# E_ink_stuff.net
KiCad netlist of a schematic drawn in Altium Designer
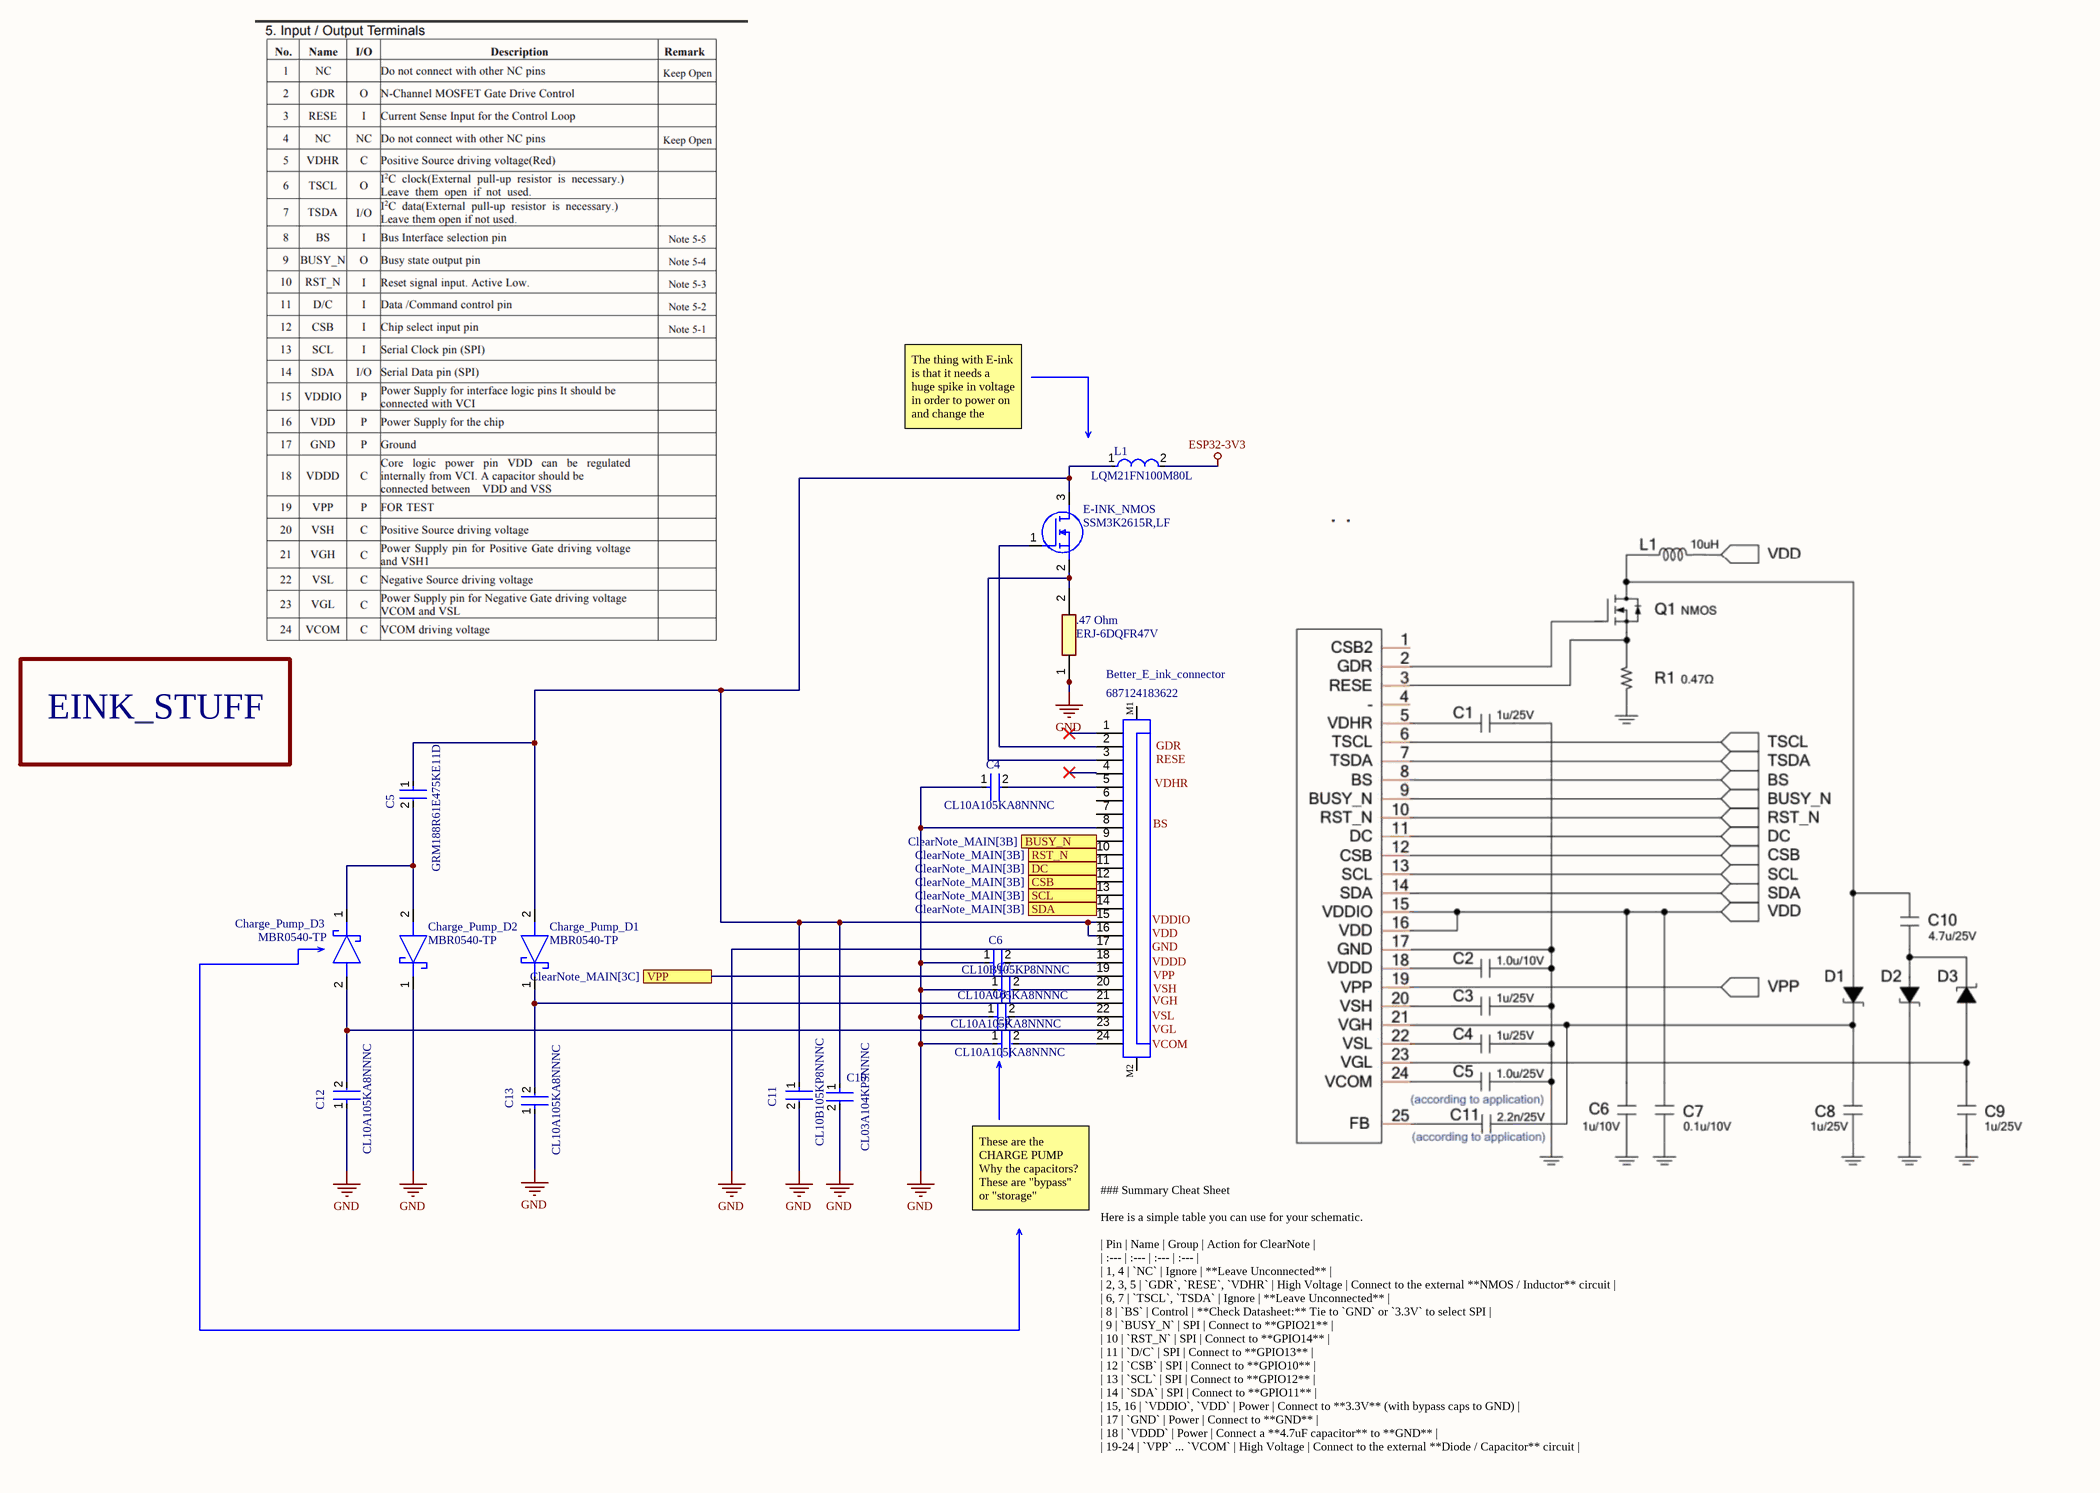
[diagram p0: E_ink_stuff.SchDoc]

(export (version "E")
  (design (tool "Eeschema 10.0.6"))
  (components
    (comp (ref ".47 Ohm")
      (value "ERJ-6DQFR47V")
      (footprint "SamacSys:ERJ6_B_BW_R_LW_CW_D")
      (description "Resistor")
      (fields (field (name "MOUSER PART NUMBER") "667-ERJ-6DQFR47V"))
      (libsource (lib "*") (part "ERJ-6DQFR47V"))
    )
    (comp (ref "Better_E_ink_connector")
      (value "687124183622")
      (footprint "687124183622")
      (libsource (lib "Altium Content Vault") (part "FPC - 24P - 2MP"))
    )
    (comp (ref "C4")
      (value "CL10A105KA8NNNC")
      (footprint "FP-CL10-IPC_C")
      (description "Cap Ceramic 1uF 25V X5R ±10% Pad SMD 0603 +85°C T/R")
      (fields (field (name "VOLTAGE") "25V") (field (name "TOLERANCE") "10%"))
      (libsource (lib "Altium Content Vault") (part "b4654b650e69147ec39a6b967a45e02"))
    )
    (comp (ref "C5")
      (value "GRM188R61E475KE11D")
      (footprint "FP-GRM188-0_15-IPC_C")
      (description "Chip Multilayer Ceramic Capacitors for General Purpose, 0603, 4.7uF, X5R, 15%, 10%, 25V")
      (fields (field (name "VOLTAGE") "25V") (field (name "TOLERANCE") "10%"))
      (libsource (lib "Altium Content Vault") (part "02cd4be3c70576c341d710602a673aa"))
    )
    (comp (ref "C6")
      (value "CL10B105KP8NNNC")
      (footprint "FP-CL10-IPC_C")
      (description "Cap Ceramic 1uF 10V X7R ±10% Pad SMD 0603 +125°C T/R")
      (fields (field (name "TOLERANCE") "10%"))
      (libsource (lib "Altium Content Vault") (part "b4654b650e69147ec39a6b967a45e02"))
    )
    (comp (ref "C7")
      (value "CL10A105KA8NNNC")
      (footprint "FP-CL10-IPC_C")
      (description "Cap Ceramic 1uF 25V X5R ±10% Pad SMD 0603 +85°C T/R")
      (fields (field (name "VOLTAGE") "25V") (field (name "TOLERANCE") "10%"))
      (libsource (lib "Altium Content Vault") (part "b4654b650e69147ec39a6b967a45e02"))
    )
    (comp (ref "C8")
      (value "CL10A105KA8NNNC")
      (footprint "FP-CL10-IPC_C")
      (description "Cap Ceramic 1uF 25V X5R ±10% Pad SMD 0603 +85°C T/R")
      (fields (field (name "VOLTAGE") "25V") (field (name "TOLERANCE") "10%"))
      (libsource (lib "Altium Content Vault") (part "b4654b650e69147ec39a6b967a45e02"))
    )
    (comp (ref "C9")
      (value "CL10A105KA8NNNC")
      (footprint "FP-CL10-IPC_C")
      (description "Cap Ceramic 1uF 25V X5R ±10% Pad SMD 0603 +85°C T/R")
      (fields (field (name "VOLTAGE") "25V") (field (name "TOLERANCE") "10%"))
      (libsource (lib "Altium Content Vault") (part "b4654b650e69147ec39a6b967a45e02"))
    )
    (comp (ref "C10")
      (value "CL03A104KP3NNNC")
      (footprint "FP-CL03-IPC_C")
      (description "Cap Ceramic 100nF 10V X5R ±10% Pad SMD 0201 +85°C T/R")
      (fields (field (name "TOLERANCE") "10%"))
      (libsource (lib "Altium Content Vault") (part "b4654b650e69147ec39a6b967a45e02"))
    )
    (comp (ref "C11")
      (value "CL10B105KP8NNNC")
      (footprint "FP-CL10-IPC_C")
      (description "Cap Ceramic 1uF 10V X7R ±10% Pad SMD 0603 +125°C T/R")
      (fields (field (name "TOLERANCE") "10%"))
      (libsource (lib "Altium Content Vault") (part "b4654b650e69147ec39a6b967a45e02"))
    )
    (comp (ref "C12")
      (value "CL10A105KA8NNNC")
      (footprint "FP-CL10-IPC_C")
      (description "Cap Ceramic 1uF 25V X5R ±10% Pad SMD 0603 +85°C T/R")
      (fields (field (name "VOLTAGE") "25V") (field (name "TOLERANCE") "10%"))
      (libsource (lib "Altium Content Vault") (part "b4654b650e69147ec39a6b967a45e02"))
    )
    (comp (ref "C13")
      (value "CL10A105KA8NNNC")
      (footprint "FP-CL10-IPC_C")
      (description "Cap Ceramic 1uF 25V X5R ±10% Pad SMD 0603 +85°C T/R")
      (fields (field (name "VOLTAGE") "25V") (field (name "TOLERANCE") "10%"))
      (libsource (lib "Altium Content Vault") (part "b4654b650e69147ec39a6b967a45e02"))
    )
    (comp (ref "Charge_Pump_D1")
      (value "MBR0540-TP")
      (footprint "SamacSys:SOD3716X135N")
      (description "Schottky Diode")
      (fields (field (name "MOUSER PART NUMBER") "833-MBR0540-TP"))
      (libsource (lib "*") (part "MBR0540-TP"))
    )
    (comp (ref "Charge_Pump_D2")
      (value "MBR0540-TP")
      (footprint "SamacSys:SOD3716X135N")
      (description "Schottky Diode")
      (fields (field (name "MOUSER PART NUMBER") "833-MBR0540-TP"))
      (libsource (lib "*") (part "MBR0540-TP"))
    )
    (comp (ref "Charge_Pump_D3")
      (value "MBR0540-TP")
      (footprint "SamacSys:SOD3716X135N")
      (description "Schottky Diode")
      (fields (field (name "MOUSER PART NUMBER") "833-MBR0540-TP"))
      (libsource (lib "*") (part "MBR0540-TP"))
    )
    (comp (ref "E-INK_NMOS")
      (value "SSM3K2615R,LF")
      (footprint "SamacSys:SOTFL95P240X88-3N")
      (description "MOSFET (N-Channel)")
      (fields (field (name "MOUSER PART NUMBER") "757-SSM3K2615RLF"))
      (libsource (lib "*") (part "SSM3K2615R,LF"))
    )
    (comp (ref "L1")
      (value "LQM21FN100M80L")
      (footprint "FP-LQM21DH_70-IPC_C")
      (description "Multilayer Type Inductor for Power Lines, 0805 (2012), 10μH, 20%, 0.39Ω, 100mA")
      (fields (field (name "TOLERANCE") "20%"))
      (libsource (lib "Altium Content Vault") (part "725321dda6339637d4d059423bc1c3c"))
    )
  )
  (nets
    (net (code "1") (name "/BUSY_N") (class "Default")
      (node (ref "Better_E_ink_connector") (pin "9") (pinfunction "9_9") (pintype "passive"))
    )
    (net (code "2") (name "/CSB") (class "Default")
      (node (ref "Better_E_ink_connector") (pin "12") (pinfunction "12_12") (pintype "passive"))
    )
    (net (code "3") (name "/DC") (class "Default")
      (node (ref "Better_E_ink_connector") (pin "11") (pinfunction "11_11") (pintype "passive"))
    )
    (net (code "4") (name "/RST_N") (class "Default")
      (node (ref "Better_E_ink_connector") (pin "10") (pinfunction "10_10") (pintype "passive"))
    )
    (net (code "5") (name "/SCL") (class "Default")
      (node (ref "Better_E_ink_connector") (pin "13") (pinfunction "13_13") (pintype "passive"))
    )
    (net (code "6") (name "/SDA") (class "Default")
      (node (ref "Better_E_ink_connector") (pin "14") (pinfunction "14_14") (pintype "passive"))
    )
    (net (code "7") (name "/VPP") (class "Default")
      (node (ref "Better_E_ink_connector") (pin "19") (pinfunction "19_19") (pintype "passive"))
    )
    (net (code "8") (name "ESP32-3V3") (class "Default")
      (node (ref "L1") (pin "2") (pinfunction "2_2") (pintype "passive"))
    )
    (net (code "9") (name "GND") (class "Default")
      (node (ref ".47 Ohm") (pin "1") (pinfunction "1_1") (pintype "passive"))
      (node (ref "Better_E_ink_connector") (pin "17") (pinfunction "17_17") (pintype "passive"))
      (node (ref "Better_E_ink_connector") (pin "8") (pinfunction "8_8") (pintype "passive"))
      (node (ref "C10") (pin "2") (pinfunction "2_2") (pintype "passive"))
      (node (ref "C11") (pin "2") (pinfunction "2_2") (pintype "passive"))
      (node (ref "C12") (pin "1") (pinfunction "1_1") (pintype "passive"))
      (node (ref "C13") (pin "1") (pinfunction "1_1") (pintype "passive"))
      (node (ref "C4") (pin "1") (pinfunction "1_1") (pintype "passive"))
      (node (ref "C6") (pin "1") (pinfunction "1_1") (pintype "passive"))
      (node (ref "C7") (pin "1") (pinfunction "1_1") (pintype "passive"))
      (node (ref "C8") (pin "1") (pinfunction "1_1") (pintype "passive"))
      (node (ref "C9") (pin "1") (pinfunction "1_1") (pintype "passive"))
      (node (ref "Charge_Pump_D2") (pin "1") (pinfunction "K_1") (pintype "passive"))
    )
    (net (code "10") (name "Net-(Better_E_ink_connector-Pad5)") (class "Default")
      (node (ref "Better_E_ink_connector") (pin "5") (pinfunction "5_5") (pintype "passive"))
      (node (ref "C4") (pin "2") (pinfunction "2_2") (pintype "passive"))
    )
    (net (code "11") (name "Net-(Better_E_ink_connector-Pad18)") (class "Default")
      (node (ref "Better_E_ink_connector") (pin "18") (pinfunction "18_18") (pintype "passive"))
      (node (ref "C6") (pin "2") (pinfunction "2_2") (pintype "passive"))
    )
    (net (code "12") (name "Net-(Better_E_ink_connector-Pad20)") (class "Default")
      (node (ref "Better_E_ink_connector") (pin "20") (pinfunction "20_20") (pintype "passive"))
      (node (ref "C7") (pin "2") (pinfunction "2_2") (pintype "passive"))
    )
    (net (code "13") (name "Net-(Better_E_ink_connector-Pad22)") (class "Default")
      (node (ref "Better_E_ink_connector") (pin "22") (pinfunction "22_22") (pintype "passive"))
      (node (ref "C8") (pin "2") (pinfunction "2_2") (pintype "passive"))
    )
    (net (code "14") (name "Net-(Better_E_ink_connector-Pad24)") (class "Default")
      (node (ref "Better_E_ink_connector") (pin "24") (pinfunction "24_24") (pintype "passive"))
      (node (ref "C9") (pin "2") (pinfunction "2_2") (pintype "passive"))
    )
    (net (code "15") (name "Net-(Charge_Pump_D1-A)") (class "Default")
      (node (ref "Better_E_ink_connector") (pin "15") (pinfunction "15_15") (pintype "passive"))
      (node (ref "Better_E_ink_connector") (pin "16") (pinfunction "16_16") (pintype "passive"))
      (node (ref "C10") (pin "1") (pinfunction "1_1") (pintype "passive"))
      (node (ref "C11") (pin "1") (pinfunction "1_1") (pintype "passive"))
      (node (ref "C5") (pin "1") (pinfunction "1_1") (pintype "passive"))
      (node (ref "Charge_Pump_D1") (pin "2") (pinfunction "A_2") (pintype "passive"))
      (node (ref "E-INK_NMOS") (pin "3") (pinfunction "D_3") (pintype "passive"))
      (node (ref "L1") (pin "1") (pinfunction "1_1") (pintype "passive"))
    )
    (net (code "16") (name "Net-(Charge_Pump_D1-K)") (class "Default")
      (node (ref "Better_E_ink_connector") (pin "21") (pinfunction "21_21") (pintype "passive"))
      (node (ref "C13") (pin "2") (pinfunction "2_2") (pintype "passive"))
      (node (ref "Charge_Pump_D1") (pin "1") (pinfunction "K_1") (pintype "passive"))
    )
    (net (code "17") (name "Net-(Charge_Pump_D2-A)") (class "Default")
      (node (ref "C5") (pin "2") (pinfunction "2_2") (pintype "passive"))
      (node (ref "Charge_Pump_D2") (pin "2") (pinfunction "A_2") (pintype "passive"))
      (node (ref "Charge_Pump_D3") (pin "1") (pinfunction "K_1") (pintype "passive"))
    )
    (net (code "18") (name "Net-(Charge_Pump_D3-A)") (class "Default")
      (node (ref "Better_E_ink_connector") (pin "23") (pinfunction "23_23") (pintype "passive"))
      (node (ref "C12") (pin "2") (pinfunction "2_2") (pintype "passive"))
      (node (ref "Charge_Pump_D3") (pin "2") (pinfunction "A_2") (pintype "passive"))
    )
    (net (code "19") (name "Net-(E-INK_NMOS-G)") (class "Default")
      (node (ref "Better_E_ink_connector") (pin "2") (pinfunction "2_2") (pintype "passive"))
      (node (ref "E-INK_NMOS") (pin "1") (pinfunction "G_1") (pintype "passive"))
    )
    (net (code "20") (name "Net-(E-INK_NMOS-S)") (class "Default")
      (node (ref ".47 Ohm") (pin "2") (pinfunction "2_2") (pintype "passive"))
      (node (ref "Better_E_ink_connector") (pin "3") (pinfunction "3_3") (pintype "passive"))
      (node (ref "E-INK_NMOS") (pin "2") (pinfunction "S_2") (pintype "passive"))
    )
    (net (code "21") (name "unconnected-(Better_E_ink_connector-Pad1)") (class "Default")
      (node (ref "Better_E_ink_connector") (pin "1") (pinfunction "1_1") (pintype "passive+no_connect"))
    )
    (net (code "22") (name "unconnected-(Better_E_ink_connector-Pad4)") (class "Default")
      (node (ref "Better_E_ink_connector") (pin "4") (pinfunction "4_4") (pintype "passive+no_connect"))
    )
    (net (code "23") (name "unconnected-(Better_E_ink_connector-Pad6)") (class "Default")
      (node (ref "Better_E_ink_connector") (pin "6") (pinfunction "6_6") (pintype "passive"))
    )
    (net (code "24") (name "unconnected-(Better_E_ink_connector-Pad7)") (class "Default")
      (node (ref "Better_E_ink_connector") (pin "7") (pinfunction "7_7") (pintype "passive"))
    )
    (net (code "25") (name "unconnected-(Better_E_ink_connector-PadM1)") (class "Default")
      (node (ref "Better_E_ink_connector") (pin "M1") (pinfunction "M1_M1") (pintype "passive"))
    )
    (net (code "26") (name "unconnected-(Better_E_ink_connector-PadM2)") (class "Default")
      (node (ref "Better_E_ink_connector") (pin "M2") (pinfunction "M2_M2") (pintype "passive"))
    )
  )
)
